# ardunio-physics-board-v2.net
KiCad netlist of a schematic drawn in EAGLE
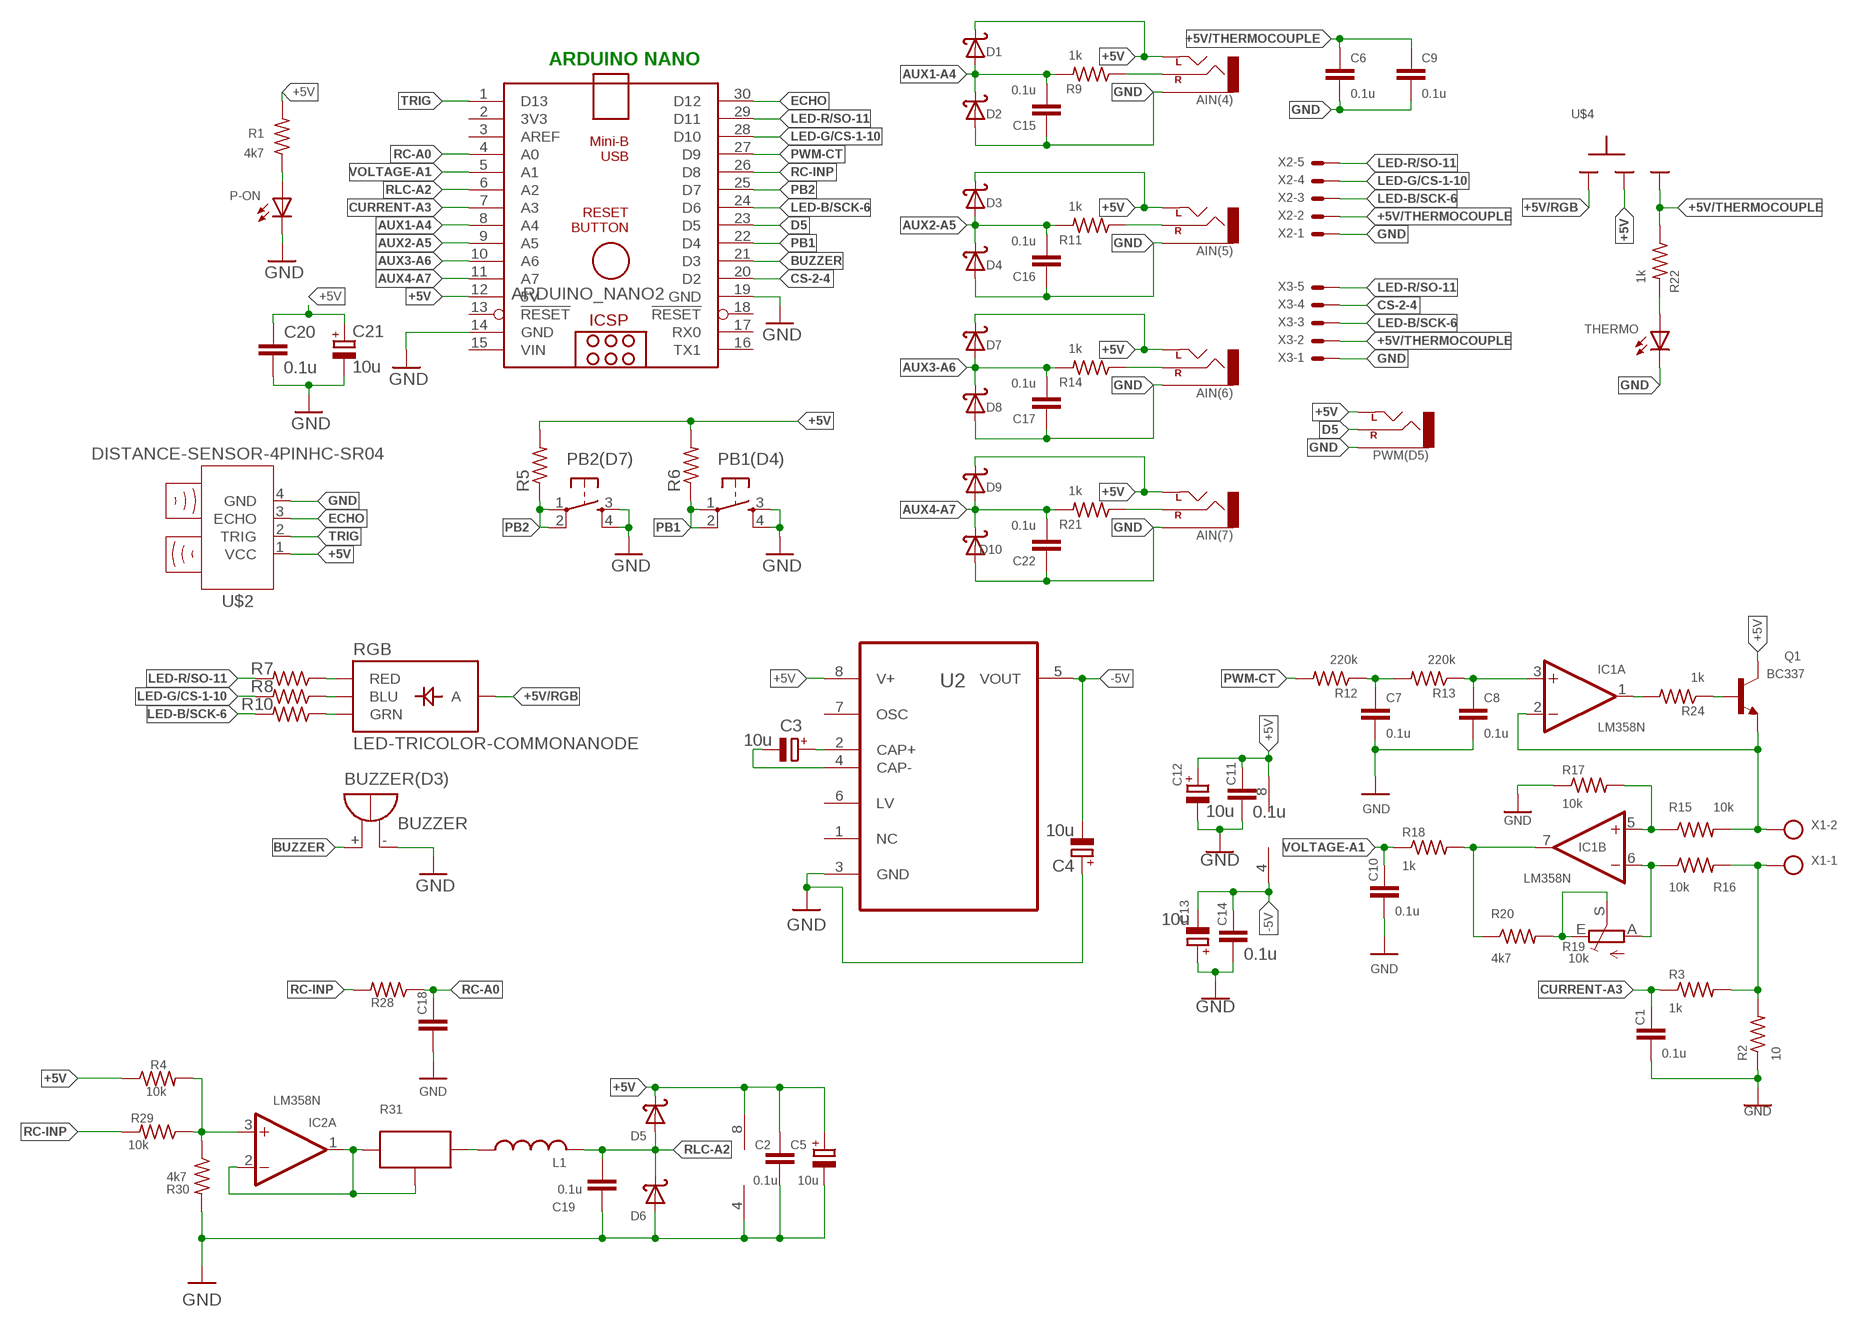
[diagram p0: schematic, sheet 1]

(export (version "E")
  (design (tool "Eeschema 10.0.6"))
  (components
    (comp (ref "AIN(4)")
      (value "AUX-CONNECTOR_CEDT_JANUARY_2015_V5_AUDIO-JACKPTH")
      (footprint "eagle-import:AUX-CONNECTOR_CEDT_JANUARY_2015_V5_AUDIO-JACK")
      (libsource (lib "eagle-import") (part "AUX-CONNECTOR_CEDT_JANUARY_2015_V5_AUDIO-JACKPTH"))
    )
    (comp (ref "AIN(5)")
      (value "AUX-CONNECTOR_CEDT_JANUARY_2015_V5_AUDIO-JACKPTH")
      (footprint "eagle-import:AUX-CONNECTOR_CEDT_JANUARY_2015_V5_AUDIO-JACK")
      (libsource (lib "eagle-import") (part "AUX-CONNECTOR_CEDT_JANUARY_2015_V5_AUDIO-JACKPTH"))
    )
    (comp (ref "AIN(6)")
      (value "AUX-CONNECTOR_CEDT_JANUARY_2015_V5_AUDIO-JACKPTH")
      (footprint "eagle-import:AUX-CONNECTOR_CEDT_JANUARY_2015_V5_AUDIO-JACK")
      (libsource (lib "eagle-import") (part "AUX-CONNECTOR_CEDT_JANUARY_2015_V5_AUDIO-JACKPTH"))
    )
    (comp (ref "AIN(7)")
      (value "AUX-CONNECTOR_CEDT_JANUARY_2015_V5_AUDIO-JACKPTH")
      (footprint "eagle-import:AUX-CONNECTOR_CEDT_JANUARY_2015_V5_AUDIO-JACK")
      (libsource (lib "eagle-import") (part "AUX-CONNECTOR_CEDT_JANUARY_2015_V5_AUDIO-JACKPTH"))
    )
    (comp (ref "ARDUINO_NANO2")
      (value "ARDUINONANOV30_ARDUINO_NANO")
      (footprint "eagle-import:ARDUINONANOV30_ARDUINO_NANO")
      (libsource (lib "eagle-import") (part "ARDUINONANOV30_ARDUINO_NANO"))
    )
    (comp (ref "BUZZER(D3)")
      (value "BUZZER")
      (footprint "eagle-import:F_TMB")
      (libsource (lib "eagle-import") (part "BUZZER"))
    )
    (comp (ref "C1")
      (value "0.1u")
      (footprint "eagle-import:C025-025X050")
      (libsource (lib "eagle-import") (part "C-EU025-025X050"))
    )
    (comp (ref "C2")
      (value "0.1u")
      (footprint "eagle-import:C025-025X050")
      (libsource (lib "eagle-import") (part "C-EU025-025X050"))
    )
    (comp (ref "C3")
      (value "10u")
      (footprint "eagle-import:TT2D5")
      (libsource (lib "eagle-import") (part "CPOL-EUTT2D5"))
    )
    (comp (ref "C4")
      (value "10u")
      (footprint "eagle-import:TT2D5")
      (libsource (lib "eagle-import") (part "CPOL-EUTT2D5"))
    )
    (comp (ref "C5")
      (value "10u")
      (footprint "eagle-import:TT2D5")
      (libsource (lib "eagle-import") (part "CPOL-EUTT2D5"))
    )
    (comp (ref "C6")
      (value "0.1u")
      (footprint "eagle-import:C025-024X044")
      (libsource (lib "eagle-import") (part "C-EU025-024X044"))
    )
    (comp (ref "C7")
      (value "0.1u")
      (footprint "eagle-import:C025-025X050")
      (libsource (lib "eagle-import") (part "C-EU025-025X050"))
    )
    (comp (ref "C8")
      (value "0.1u")
      (footprint "eagle-import:C025-025X050")
      (libsource (lib "eagle-import") (part "C-EU025-025X050"))
    )
    (comp (ref "C9")
      (value "0.1u")
      (footprint "eagle-import:C025-024X044")
      (libsource (lib "eagle-import") (part "C-EU025-024X044"))
    )
    (comp (ref "C10")
      (value "0.1u")
      (footprint "eagle-import:C025-025X050")
      (libsource (lib "eagle-import") (part "C-EU025-025X050"))
    )
    (comp (ref "C11")
      (value "0.1u")
      (footprint "eagle-import:C025-025X050")
      (libsource (lib "eagle-import") (part "C-EU025-025X050"))
    )
    (comp (ref "C12")
      (value "10u")
      (footprint "eagle-import:TT2D5")
      (libsource (lib "eagle-import") (part "CPOL-EUTT2D5"))
    )
    (comp (ref "C13")
      (value "10u")
      (footprint "eagle-import:TT2D5")
      (libsource (lib "eagle-import") (part "CPOL-EUTT2D5"))
    )
    (comp (ref "C14")
      (value "0.1u")
      (footprint "eagle-import:C025-025X050")
      (libsource (lib "eagle-import") (part "C-EU025-025X050"))
    )
    (comp (ref "C15")
      (value "0.1u")
      (footprint "eagle-import:C025-024X044")
      (libsource (lib "eagle-import") (part "C-EU025-024X044"))
    )
    (comp (ref "C16")
      (value "0.1u")
      (footprint "eagle-import:C025-024X044")
      (libsource (lib "eagle-import") (part "C-EU025-024X044"))
    )
    (comp (ref "C17")
      (value "0.1u")
      (footprint "eagle-import:C025-024X044")
      (libsource (lib "eagle-import") (part "C-EU025-024X044"))
    )
    (comp (ref "C18")
      (value "C-EU025-025X050")
      (footprint "eagle-import:C025-025X050")
      (libsource (lib "eagle-import") (part "C-EU025-025X050"))
    )
    (comp (ref "C19")
      (value "0.1u")
      (footprint "eagle-import:C025-025X050")
      (libsource (lib "eagle-import") (part "C-EU025-025X050"))
    )
    (comp (ref "C20")
      (value "0.1u")
      (footprint "eagle-import:C025-024X044")
      (libsource (lib "eagle-import") (part "C-EU025-024X044"))
    )
    (comp (ref "C21")
      (value "10u")
      (footprint "eagle-import:E2,5-5")
      (libsource (lib "eagle-import") (part "CPOL-EUE2.5-5"))
    )
    (comp (ref "C22")
      (value "0.1u")
      (footprint "eagle-import:C025-024X044")
      (libsource (lib "eagle-import") (part "C-EU025-024X044"))
    )
    (comp (ref "D1")
      (value "1N5819")
      (footprint "eagle-import:DO41-10")
      (libsource (lib "eagle-import") (part "1N5819"))
    )
    (comp (ref "D2")
      (value "1N5819")
      (footprint "eagle-import:DO41-10")
      (libsource (lib "eagle-import") (part "1N5819"))
    )
    (comp (ref "D3")
      (value "1N5819")
      (footprint "eagle-import:DO41-10")
      (libsource (lib "eagle-import") (part "1N5819"))
    )
    (comp (ref "D4")
      (value "1N5819")
      (footprint "eagle-import:DO41-10")
      (libsource (lib "eagle-import") (part "1N5819"))
    )
    (comp (ref "D5")
      (value "1N5819")
      (footprint "eagle-import:DO41-10")
      (libsource (lib "eagle-import") (part "1N5819"))
    )
    (comp (ref "D6")
      (value "1N5819")
      (footprint "eagle-import:DO41-10")
      (libsource (lib "eagle-import") (part "1N5819"))
    )
    (comp (ref "D7")
      (value "1N5819")
      (footprint "eagle-import:DO41-10")
      (libsource (lib "eagle-import") (part "1N5819"))
    )
    (comp (ref "D8")
      (value "1N5819")
      (footprint "eagle-import:DO41-10")
      (libsource (lib "eagle-import") (part "1N5819"))
    )
    (comp (ref "D9")
      (value "1N5819")
      (footprint "eagle-import:DO41-10")
      (libsource (lib "eagle-import") (part "1N5819"))
    )
    (comp (ref "D10")
      (value "1N5819")
      (footprint "eagle-import:DO41-10")
      (libsource (lib "eagle-import") (part "1N5819"))
    )
    (comp (ref "IC1")
      (value "LM358N")
      (footprint "eagle-import:DIL08")
      (libsource (lib "eagle-import") (part "LM358N"))
    )
    (comp (ref "IC2")
      (value "LM358N")
      (footprint "eagle-import:DIL08")
      (libsource (lib "eagle-import") (part "LM358N"))
    )
    (comp (ref "L1")
      (value "L-US6000-XXX-RC")
      (footprint "eagle-import:6000-XXXX-RC")
      (libsource (lib "eagle-import") (part "L-US6000-XXX-RC"))
    )
    (comp (ref "P-ON")
      (value "LED3MM")
      (footprint "eagle-import:LED3MM")
      (libsource (lib "eagle-import") (part "LED3MM"))
    )
    (comp (ref "PB1(D4)")
      (value "OMRON_SWITCH_40-XX")
      (footprint "eagle-import:B3F-40XX")
      (libsource (lib "eagle-import") (part "OMRON_SWITCH_40-XX"))
    )
    (comp (ref "PB2(D7)")
      (value "OMRON_SWITCH_40-XX")
      (footprint "eagle-import:B3F-40XX")
      (libsource (lib "eagle-import") (part "OMRON_SWITCH_40-XX"))
    )
    (comp (ref "PWM(D5)")
      (value "AUX-CONNECTOR_CEDT_JANUARY_2015_V5_AUDIO-JACKPTH")
      (footprint "eagle-import:AUX-CONNECTOR_CEDT_JANUARY_2015_V5_AUDIO-JACK")
      (libsource (lib "eagle-import") (part "AUX-CONNECTOR_CEDT_JANUARY_2015_V5_AUDIO-JACKPTH"))
    )
    (comp (ref "Q1")
      (value "BC337")
      (footprint "eagle-import:TO92")
      (libsource (lib "eagle-import") (part "BC337"))
    )
    (comp (ref "R1")
      (value "4k7")
      (footprint "eagle-import:0204_7")
      (libsource (lib "eagle-import") (part "R-US_0204/7"))
    )
    (comp (ref "R2")
      (value "10")
      (footprint "eagle-import:0207_10")
      (libsource (lib "eagle-import") (part "RESISTOR0207/10"))
    )
    (comp (ref "R3")
      (value "1k")
      (footprint "eagle-import:0204_7")
      (libsource (lib "eagle-import") (part "R-US_0204/7"))
    )
    (comp (ref "R4")
      (value "10k")
      (footprint "eagle-import:0207_10")
      (libsource (lib "eagle-import") (part "R-US_0207/10"))
    )
    (comp (ref "R5")
      (value "R-US_0204/7")
      (footprint "eagle-import:0204_7")
      (libsource (lib "eagle-import") (part "R-US_0204/7"))
    )
    (comp (ref "R6")
      (value "R-US_0204/7")
      (footprint "eagle-import:0204_7")
      (libsource (lib "eagle-import") (part "R-US_0204/7"))
    )
    (comp (ref "R7")
      (value "R-US_0207/10")
      (footprint "eagle-import:0207_10")
      (libsource (lib "eagle-import") (part "R-US_0207/10"))
    )
    (comp (ref "R8")
      (value "R-US_0207/10")
      (footprint "eagle-import:0207_10")
      (libsource (lib "eagle-import") (part "R-US_0207/10"))
    )
    (comp (ref "R9")
      (value "1k")
      (footprint "eagle-import:0204_7")
      (libsource (lib "eagle-import") (part "R-US_0204/7"))
    )
    (comp (ref "R10")
      (value "R-US_0207/10")
      (footprint "eagle-import:0207_10")
      (libsource (lib "eagle-import") (part "R-US_0207/10"))
    )
    (comp (ref "R11")
      (value "1k")
      (footprint "eagle-import:0204_7")
      (libsource (lib "eagle-import") (part "R-US_0204/7"))
    )
    (comp (ref "R12")
      (value "220k")
      (footprint "eagle-import:0207_10")
      (libsource (lib "eagle-import") (part "R-US_0207/10"))
    )
    (comp (ref "R13")
      (value "220k")
      (footprint "eagle-import:0204_7")
      (libsource (lib "eagle-import") (part "R-US_0204/7"))
    )
    (comp (ref "R14")
      (value "1k")
      (footprint "eagle-import:0204_7")
      (libsource (lib "eagle-import") (part "R-US_0204/7"))
    )
    (comp (ref "R15")
      (value "10k")
      (footprint "eagle-import:0204_7")
      (libsource (lib "eagle-import") (part "R-US_0204/7"))
    )
    (comp (ref "R16")
      (value "10k")
      (footprint "eagle-import:0204_7")
      (libsource (lib "eagle-import") (part "R-US_0204/7"))
    )
    (comp (ref "R17")
      (value "10k")
      (footprint "eagle-import:0204_7")
      (libsource (lib "eagle-import") (part "R-US_0204/7"))
    )
    (comp (ref "R18")
      (value "1k")
      (footprint "eagle-import:0204_7")
      (libsource (lib "eagle-import") (part "R-US_0204/7"))
    )
    (comp (ref "R19")
      (value "10k")
      (footprint "eagle-import:RJ9W")
      (libsource (lib "eagle-import") (part "TRIM_EU-RJ9W"))
    )
    (comp (ref "R20")
      (value "4k7")
      (footprint "eagle-import:0204_7")
      (libsource (lib "eagle-import") (part "R-US_0204/7"))
    )
    (comp (ref "R21")
      (value "1k")
      (footprint "eagle-import:0204_7")
      (libsource (lib "eagle-import") (part "R-US_0204/7"))
    )
    (comp (ref "R22")
      (value "1k")
      (footprint "eagle-import:0204_7")
      (libsource (lib "eagle-import") (part "R-US_0204/7"))
    )
    (comp (ref "R24")
      (value "1k")
      (footprint "eagle-import:0204_7")
      (libsource (lib "eagle-import") (part "R-US_0204/7"))
    )
    (comp (ref "R28")
      (value "R-US_0207/10")
      (footprint "eagle-import:0207_10")
      (libsource (lib "eagle-import") (part "R-US_0207/10"))
    )
    (comp (ref "R29")
      (value "10k")
      (footprint "eagle-import:0204_7")
      (libsource (lib "eagle-import") (part "R-US_0204/7"))
    )
    (comp (ref "R30")
      (value "4k7")
      (footprint "eagle-import:0207_10")
      (libsource (lib "eagle-import") (part "R-US_0207/10"))
    )
    (comp (ref "R31")
      (value "POTNORMAL")
      (footprint "eagle-import:RJ9W")
      (libsource (lib "eagle-import") (part "POTNORMAL"))
    )
    (comp (ref "RGB")
      (value "LED-TRICOLOR-COMMONANODE")
      (footprint "eagle-import:LED-TRICOLOR-THROUGHHOLE")
      (libsource (lib "eagle-import") (part "LED-TRICOLOR-COMMONANODE"))
    )
    (comp (ref "THERMO")
      (value "LED3MM")
      (footprint "eagle-import:LED3MM")
      (libsource (lib "eagle-import") (part "LED3MM"))
    )
    (comp (ref "U$2")
      (value "DISTANCE-SENSOR-4PINHC-SR04")
      (footprint "eagle-import:HC-SR04")
      (libsource (lib "eagle-import") (part "DISTANCE-SENSOR-4PINHC-SR04"))
    )
    (comp (ref "U$4")
      (value "SLIDESWITCH-BIG")
      (footprint "eagle-import:BIGSWITCH")
      (libsource (lib "eagle-import") (part "SLIDESWITCH-BIG"))
    )
    (comp (ref "U2")
      (value "ICL7660CPAZ_ICL7660CPAZ")
      (footprint "eagle-import:ICL7660CPAZ_DIP254P762X533-8")
      (fields (field (name "MF") "Renesas Electronics") (field (name "MP") "ICL7660CPAZ"))
      (libsource (lib "eagle-import") (part "ICL7660CPAZ_ICL7660CPAZ"))
    )
    (comp (ref "X1")
      (value "AK500/2-H")
      (footprint "eagle-import:AK500_2-H")
      (libsource (lib "eagle-import") (part "AK500/2-H"))
    )
    (comp (ref "X2")
      (value "JST-XH-05-PIN-LONG-PAD")
      (footprint "eagle-import:JST-XH-05-PACKAGE-LONG-PAD")
      (libsource (lib "eagle-import") (part "JST-XH-05-PIN-LONG-PAD"))
    )
    (comp (ref "X3")
      (value "JST-XH-05-PIN-LONG-PAD")
      (footprint "eagle-import:JST-XH-05-PACKAGE-LONG-PAD")
      (libsource (lib "eagle-import") (part "JST-XH-05-PIN-LONG-PAD"))
    )
  )
  (nets
    (net (code "1") (name "+5V") (class "Default")
      (node (ref "AIN(4)") (pin "TIP") (pinfunction "LEFT_TIP") (pintype "bidirectional"))
      (node (ref "AIN(5)") (pin "TIP") (pinfunction "LEFT_TIP") (pintype "bidirectional"))
      (node (ref "AIN(6)") (pin "TIP") (pinfunction "LEFT_TIP") (pintype "bidirectional"))
      (node (ref "AIN(7)") (pin "TIP") (pinfunction "LEFT_TIP") (pintype "bidirectional"))
      (node (ref "ARDUINO_NANO2") (pin "12") (pinfunction "5V_12") (pintype "power_in"))
      (node (ref "C11") (pin "1") (pinfunction "1_1") (pintype "passive"))
      (node (ref "C12") (pin "+") (pinfunction "+_+") (pintype "passive"))
      (node (ref "C2") (pin "1") (pinfunction "1_1") (pintype "passive"))
      (node (ref "C20") (pin "1") (pinfunction "1_1") (pintype "passive"))
      (node (ref "C21") (pin "+") (pinfunction "+_+") (pintype "passive"))
      (node (ref "C5") (pin "+") (pinfunction "+_+") (pintype "passive"))
      (node (ref "D1") (pin "C") (pinfunction "C_C") (pintype "passive"))
      (node (ref "D3") (pin "C") (pinfunction "C_C") (pintype "passive"))
      (node (ref "D5") (pin "C") (pinfunction "C_C") (pintype "passive"))
      (node (ref "D7") (pin "C") (pinfunction "C_C") (pintype "passive"))
      (node (ref "D9") (pin "C") (pinfunction "C_C") (pintype "passive"))
      (node (ref "IC1") (pin "8") (pinfunction "V+_8") (pintype "power_in"))
      (node (ref "IC2") (pin "8") (pinfunction "V+_8") (pintype "power_in"))
      (node (ref "PWM(D5)") (pin "TIP") (pinfunction "LEFT_TIP") (pintype "bidirectional"))
      (node (ref "Q1") (pin "3") (pinfunction "C_3") (pintype "passive"))
      (node (ref "R1") (pin "2") (pinfunction "2_2") (pintype "passive"))
      (node (ref "R4") (pin "1") (pinfunction "1_1") (pintype "passive"))
      (node (ref "R5") (pin "2") (pinfunction "2_2") (pintype "passive"))
      (node (ref "R6") (pin "2") (pinfunction "2_2") (pintype "passive"))
      (node (ref "U$2") (pin "1") (pinfunction "VCC_1") (pintype "bidirectional"))
      (node (ref "U$4") (pin "2") (pinfunction "2_2") (pintype "bidirectional"))
      (node (ref "U2") (pin "8") (pinfunction "V+_8") (pintype "power_in"))
    )
    (net (code "2") (name "+5V{slash}RGB") (class "Default")
      (node (ref "RGB") (pin "ANODE") (pinfunction "A_ANODE") (pintype "bidirectional"))
      (node (ref "U$4") (pin "1") (pinfunction "1_1") (pintype "bidirectional"))
    )
    (net (code "3") (name "+5V{slash}THERMOCOUPLE") (class "Default")
      (node (ref "C6") (pin "1") (pinfunction "1_1") (pintype "passive"))
      (node (ref "C9") (pin "1") (pinfunction "1_1") (pintype "passive"))
      (node (ref "R22") (pin "1") (pinfunction "1_1") (pintype "passive"))
      (node (ref "U$4") (pin "3") (pinfunction "3_3") (pintype "bidirectional"))
      (node (ref "X2") (pin "2") (pinfunction "S_2") (pintype "passive"))
      (node (ref "X3") (pin "2") (pinfunction "S_2") (pintype "passive"))
    )
    (net (code "4") (name "-5V") (class "Default")
      (node (ref "C13") (pin "-") (pinfunction "-_-") (pintype "passive"))
      (node (ref "C14") (pin "1") (pinfunction "1_1") (pintype "passive"))
      (node (ref "C4") (pin "-") (pinfunction "-_-") (pintype "passive"))
      (node (ref "IC1") (pin "4") (pinfunction "V-_4") (pintype "power_in"))
      (node (ref "U2") (pin "5") (pinfunction "VOUT_5") (pintype "output"))
    )
    (net (code "5") (name "/VIN") (class "Default")
      (node (ref "ARDUINO_NANO2") (pin "15") (pinfunction "VIN_15") (pintype "power_in"))
    )
    (net (code "6") (name "AUX1-A4") (class "Default")
      (node (ref "ARDUINO_NANO2") (pin "8") (pinfunction "A4_8") (pintype "bidirectional"))
      (node (ref "C15") (pin "2") (pinfunction "2_2") (pintype "passive"))
      (node (ref "D1") (pin "A") (pinfunction "A_A") (pintype "passive"))
      (node (ref "D2") (pin "C") (pinfunction "C_C") (pintype "passive"))
      (node (ref "R9") (pin "2") (pinfunction "2_2") (pintype "passive"))
    )
    (net (code "7") (name "AUX2-A5") (class "Default")
      (node (ref "ARDUINO_NANO2") (pin "9") (pinfunction "A5_9") (pintype "bidirectional"))
      (node (ref "C16") (pin "2") (pinfunction "2_2") (pintype "passive"))
      (node (ref "D3") (pin "A") (pinfunction "A_A") (pintype "passive"))
      (node (ref "D4") (pin "C") (pinfunction "C_C") (pintype "passive"))
      (node (ref "R11") (pin "2") (pinfunction "2_2") (pintype "passive"))
    )
    (net (code "8") (name "AUX3-A6") (class "Default")
      (node (ref "ARDUINO_NANO2") (pin "10") (pinfunction "A6_10") (pintype "bidirectional"))
      (node (ref "C17") (pin "2") (pinfunction "2_2") (pintype "passive"))
      (node (ref "D7") (pin "A") (pinfunction "A_A") (pintype "passive"))
      (node (ref "D8") (pin "C") (pinfunction "C_C") (pintype "passive"))
      (node (ref "R14") (pin "2") (pinfunction "2_2") (pintype "passive"))
    )
    (net (code "9") (name "AUX4-A7") (class "Default")
      (node (ref "ARDUINO_NANO2") (pin "11") (pinfunction "A7_11") (pintype "bidirectional"))
      (node (ref "C22") (pin "2") (pinfunction "2_2") (pintype "passive"))
      (node (ref "D10") (pin "C") (pinfunction "C_C") (pintype "passive"))
      (node (ref "D9") (pin "A") (pinfunction "A_A") (pintype "passive"))
      (node (ref "R21") (pin "2") (pinfunction "2_2") (pintype "passive"))
    )
    (net (code "10") (name "BUZZER") (class "Default")
      (node (ref "ARDUINO_NANO2") (pin "21") (pinfunction "D3_21") (pintype "bidirectional"))
      (node (ref "BUZZER(D3)") (pin "+") (pinfunction "+_+") (pintype "passive"))
    )
    (net (code "11") (name "CS-2-4") (class "Default")
      (node (ref "ARDUINO_NANO2") (pin "20") (pinfunction "D2_20") (pintype "bidirectional"))
      (node (ref "X3") (pin "4") (pinfunction "S_4") (pintype "passive"))
    )
    (net (code "12") (name "CURRENT-A3") (class "Default")
      (node (ref "ARDUINO_NANO2") (pin "7") (pinfunction "A3_7") (pintype "bidirectional"))
      (node (ref "C1") (pin "1") (pinfunction "1_1") (pintype "passive"))
      (node (ref "R3") (pin "1") (pinfunction "1_1") (pintype "passive"))
    )
    (net (code "13") (name "D5") (class "Default")
      (node (ref "ARDUINO_NANO2") (pin "23") (pinfunction "D5_23") (pintype "bidirectional"))
      (node (ref "PWM(D5)") (pin "RING") (pinfunction "RIGHT_RING") (pintype "bidirectional"))
    )
    (net (code "14") (name "ECHO") (class "Default")
      (node (ref "ARDUINO_NANO2") (pin "30") (pinfunction "D12_30") (pintype "bidirectional"))
      (node (ref "U$2") (pin "3") (pinfunction "ECHO_3") (pintype "bidirectional"))
    )
    (net (code "15") (name "GND") (class "Default")
      (node (ref "AIN(4)") (pin "SLEEVE") (pinfunction "SLEEVE_SLEEVE") (pintype "bidirectional"))
      (node (ref "AIN(5)") (pin "SLEEVE") (pinfunction "SLEEVE_SLEEVE") (pintype "bidirectional"))
      (node (ref "AIN(6)") (pin "SLEEVE") (pinfunction "SLEEVE_SLEEVE") (pintype "bidirectional"))
      (node (ref "AIN(7)") (pin "SLEEVE") (pinfunction "SLEEVE_SLEEVE") (pintype "bidirectional"))
      (node (ref "ARDUINO_NANO2") (pin "14") (pinfunction "GND_14") (pintype "power_in"))
      (node (ref "ARDUINO_NANO2") (pin "19") (pinfunction "GND_19") (pintype "power_in"))
      (node (ref "BUZZER(D3)") (pin "-") (pinfunction "-_-") (pintype "passive"))
      (node (ref "C1") (pin "2") (pinfunction "2_2") (pintype "passive"))
      (node (ref "C10") (pin "2") (pinfunction "2_2") (pintype "passive"))
      (node (ref "C11") (pin "2") (pinfunction "2_2") (pintype "passive"))
      (node (ref "C12") (pin "-") (pinfunction "-_-") (pintype "passive"))
      (node (ref "C13") (pin "+") (pinfunction "+_+") (pintype "passive"))
      (node (ref "C14") (pin "2") (pinfunction "2_2") (pintype "passive"))
      (node (ref "C15") (pin "1") (pinfunction "1_1") (pintype "passive"))
      (node (ref "C16") (pin "1") (pinfunction "1_1") (pintype "passive"))
      (node (ref "C17") (pin "1") (pinfunction "1_1") (pintype "passive"))
      (node (ref "C18") (pin "2") (pinfunction "2_2") (pintype "passive"))
      (node (ref "C19") (pin "2") (pinfunction "2_2") (pintype "passive"))
      (node (ref "C2") (pin "2") (pinfunction "2_2") (pintype "passive"))
      (node (ref "C20") (pin "2") (pinfunction "2_2") (pintype "passive"))
      (node (ref "C21") (pin "-") (pinfunction "-_-") (pintype "passive"))
      (node (ref "C22") (pin "1") (pinfunction "1_1") (pintype "passive"))
      (node (ref "C4") (pin "+") (pinfunction "+_+") (pintype "passive"))
      (node (ref "C5") (pin "-") (pinfunction "-_-") (pintype "passive"))
      (node (ref "C6") (pin "2") (pinfunction "2_2") (pintype "passive"))
      (node (ref "C7") (pin "2") (pinfunction "2_2") (pintype "passive"))
      (node (ref "C8") (pin "2") (pinfunction "2_2") (pintype "passive"))
      (node (ref "C9") (pin "2") (pinfunction "2_2") (pintype "passive"))
      (node (ref "D10") (pin "A") (pinfunction "A_A") (pintype "passive"))
      (node (ref "D2") (pin "A") (pinfunction "A_A") (pintype "passive"))
      (node (ref "D4") (pin "A") (pinfunction "A_A") (pintype "passive"))
      (node (ref "D6") (pin "A") (pinfunction "A_A") (pintype "passive"))
      (node (ref "D8") (pin "A") (pinfunction "A_A") (pintype "passive"))
      (node (ref "IC2") (pin "4") (pinfunction "V-_4") (pintype "power_in"))
      (node (ref "P-ON") (pin "K") (pinfunction "C_K") (pintype "passive"))
      (node (ref "PB1(D4)") (pin "3") (pinfunction "S_3") (pintype "passive"))
      (node (ref "PB1(D4)") (pin "4") (pinfunction "S1_4") (pintype "passive"))
      (node (ref "PB2(D7)") (pin "3") (pinfunction "S_3") (pintype "passive"))
      (node (ref "PB2(D7)") (pin "4") (pinfunction "S1_4") (pintype "passive"))
      (node (ref "PWM(D5)") (pin "SLEEVE") (pinfunction "SLEEVE_SLEEVE") (pintype "bidirectional"))
      (node (ref "R17") (pin "1") (pinfunction "1_1") (pintype "passive"))
      (node (ref "R2") (pin "1") (pinfunction "1_1") (pintype "passive"))
      (node (ref "R30") (pin "2") (pinfunction "2_2") (pintype "passive"))
      (node (ref "THERMO") (pin "K") (pinfunction "C_K") (pintype "passive"))
      (node (ref "U$2") (pin "4") (pinfunction "GND_4") (pintype "bidirectional"))
      (node (ref "U2") (pin "3") (pinfunction "GND_3") (pintype "passive"))
      (node (ref "X2") (pin "1") (pinfunction "S_1") (pintype "passive"))
      (node (ref "X3") (pin "1") (pinfunction "S_1") (pintype "passive"))
    )
    (net (code "16") (name "LED-B{slash}SCK-6") (class "Default")
      (node (ref "ARDUINO_NANO2") (pin "24") (pinfunction "D6_24") (pintype "bidirectional"))
      (node (ref "R10") (pin "2") (pinfunction "2_2") (pintype "passive"))
      (node (ref "X2") (pin "3") (pinfunction "S_3") (pintype "passive"))
      (node (ref "X3") (pin "3") (pinfunction "S_3") (pintype "passive"))
    )
    (net (code "17") (name "LED-G{slash}CS-1-10") (class "Default")
      (node (ref "ARDUINO_NANO2") (pin "28") (pinfunction "D10_28") (pintype "bidirectional"))
      (node (ref "R8") (pin "2") (pinfunction "2_2") (pintype "passive"))
      (node (ref "X2") (pin "4") (pinfunction "S_4") (pintype "passive"))
    )
    (net (code "18") (name "LED-R{slash}SO-11") (class "Default")
      (node (ref "ARDUINO_NANO2") (pin "29") (pinfunction "D11_29") (pintype "bidirectional"))
      (node (ref "R7") (pin "2") (pinfunction "2_2") (pintype "passive"))
      (node (ref "X2") (pin "5") (pinfunction "S_5") (pintype "passive"))
      (node (ref "X3") (pin "5") (pinfunction "S_5") (pintype "passive"))
    )
    (net (code "19") (name "Net-(AIN(4)-RIGHT)") (class "Default")
      (node (ref "AIN(4)") (pin "RING") (pinfunction "RIGHT_RING") (pintype "bidirectional"))
      (node (ref "R9") (pin "1") (pinfunction "1_1") (pintype "passive"))
    )
    (net (code "20") (name "Net-(AIN(5)-RIGHT)") (class "Default")
      (node (ref "AIN(5)") (pin "RING") (pinfunction "RIGHT_RING") (pintype "bidirectional"))
      (node (ref "R11") (pin "1") (pinfunction "1_1") (pintype "passive"))
    )
    (net (code "21") (name "Net-(AIN(6)-RIGHT)") (class "Default")
      (node (ref "AIN(6)") (pin "RING") (pinfunction "RIGHT_RING") (pintype "bidirectional"))
      (node (ref "R14") (pin "1") (pinfunction "1_1") (pintype "passive"))
    )
    (net (code "22") (name "Net-(AIN(7)-RIGHT)") (class "Default")
      (node (ref "AIN(7)") (pin "RING") (pinfunction "RIGHT_RING") (pintype "bidirectional"))
      (node (ref "R21") (pin "1") (pinfunction "1_1") (pintype "passive"))
    )
    (net (code "23") (name "Net-(C7-Pad1)") (class "Default")
      (node (ref "C7") (pin "1") (pinfunction "1_1") (pintype "passive"))
      (node (ref "R12") (pin "1") (pinfunction "1_1") (pintype "passive"))
      (node (ref "R13") (pin "2") (pinfunction "2_2") (pintype "passive"))
    )
    (net (code "24") (name "Net-(IC1A-+IN)") (class "Default")
      (node (ref "C8") (pin "1") (pinfunction "1_1") (pintype "passive"))
      (node (ref "IC1") (pin "3") (pinfunction "+IN_3") (pintype "input"))
      (node (ref "R13") (pin "1") (pinfunction "1_1") (pintype "passive"))
    )
    (net (code "25") (name "Net-(IC1A--IN)") (class "Default")
      (node (ref "IC1") (pin "2") (pinfunction "-IN_2") (pintype "input"))
      (node (ref "Q1") (pin "1") (pinfunction "E_1") (pintype "passive"))
      (node (ref "R15") (pin "2") (pinfunction "2_2") (pintype "passive"))
      (node (ref "X1") (pin "2") (pinfunction "KL_2") (pintype "passive"))
    )
    (net (code "26") (name "Net-(IC1A-OUT)") (class "Default")
      (node (ref "IC1") (pin "1") (pinfunction "OUT_1") (pintype "output"))
      (node (ref "R24") (pin "2") (pinfunction "2_2") (pintype "passive"))
    )
    (net (code "27") (name "Net-(IC1B-+IN)") (class "Default")
      (node (ref "IC1") (pin "5") (pinfunction "+IN_5") (pintype "input"))
      (node (ref "R15") (pin "1") (pinfunction "1_1") (pintype "passive"))
      (node (ref "R17") (pin "2") (pinfunction "2_2") (pintype "passive"))
    )
    (net (code "28") (name "Net-(IC1B--IN)") (class "Default")
      (node (ref "IC1") (pin "6") (pinfunction "-IN_6") (pintype "input"))
      (node (ref "R16") (pin "1") (pinfunction "1_1") (pintype "passive"))
      (node (ref "R19") (pin "A") (pinfunction "A_A") (pintype "passive"))
    )
    (net (code "29") (name "Net-(IC1B-OUT)") (class "Default")
      (node (ref "IC1") (pin "7") (pinfunction "OUT_7") (pintype "output"))
      (node (ref "R18") (pin "2") (pinfunction "2_2") (pintype "passive"))
      (node (ref "R20") (pin "1") (pinfunction "1_1") (pintype "passive"))
    )
    (net (code "30") (name "Net-(IC2A-+IN)") (class "Default")
      (node (ref "IC2") (pin "3") (pinfunction "+IN_3") (pintype "input"))
      (node (ref "R29") (pin "1") (pinfunction "1_1") (pintype "passive"))
      (node (ref "R30") (pin "1") (pinfunction "1_1") (pintype "passive"))
      (node (ref "R4") (pin "2") (pinfunction "2_2") (pintype "passive"))
    )
    (net (code "31") (name "Net-(IC2A--IN)") (class "Default")
      (node (ref "IC2") (pin "1") (pinfunction "OUT_1") (pintype "output"))
      (node (ref "IC2") (pin "2") (pinfunction "-IN_2") (pintype "input"))
      (node (ref "R31") (pin "E") (pinfunction "E_E") (pintype "passive"))
      (node (ref "R31") (pin "S") (pinfunction "S_S") (pintype "passive"))
    )
    (net (code "32") (name "Net-(L1-Pad1)") (class "Default")
      (node (ref "L1") (pin "1") (pinfunction "1_1") (pintype "passive"))
      (node (ref "R31") (pin "A") (pinfunction "A_A") (pintype "passive"))
    )
    (net (code "33") (name "Net-(P-ON-PadA)") (class "Default")
      (node (ref "P-ON") (pin "A") (pinfunction "A_A") (pintype "passive"))
      (node (ref "R1") (pin "1") (pinfunction "1_1") (pintype "passive"))
    )
    (net (code "34") (name "Net-(Q1-B)") (class "Default")
      (node (ref "Q1") (pin "2") (pinfunction "B_2") (pintype "passive"))
      (node (ref "R24") (pin "1") (pinfunction "1_1") (pintype "passive"))
    )
    (net (code "35") (name "Net-(R7-Pad1)") (class "Default")
      (node (ref "R7") (pin "1") (pinfunction "1_1") (pintype "passive"))
      (node (ref "RGB") (pin "RED") (pinfunction "RED_RED") (pintype "bidirectional"))
    )
    (net (code "36") (name "Net-(R8-Pad1)") (class "Default")
      (node (ref "R8") (pin "1") (pinfunction "1_1") (pintype "passive"))
      (node (ref "RGB") (pin "BLU") (pinfunction "BLU_BLU") (pintype "bidirectional"))
    )
    (net (code "37") (name "Net-(R10-Pad1)") (class "Default")
      (node (ref "R10") (pin "1") (pinfunction "1_1") (pintype "passive"))
      (node (ref "RGB") (pin "GRN") (pinfunction "GRN_GRN") (pintype "bidirectional"))
    )
    (net (code "38") (name "Net-(R19-PadE)") (class "Default")
      (node (ref "R19") (pin "E") (pinfunction "E_E") (pintype "passive"))
      (node (ref "R19") (pin "S") (pinfunction "S_S") (pintype "passive"))
      (node (ref "R20") (pin "2") (pinfunction "2_2") (pintype "passive"))
    )
    (net (code "39") (name "Net-(R22-Pad2)") (class "Default")
      (node (ref "R22") (pin "2") (pinfunction "2_2") (pintype "passive"))
      (node (ref "THERMO") (pin "A") (pinfunction "A_A") (pintype "passive"))
    )
    (net (code "40") (name "Net-(U2-CAP+)") (class "Default")
      (node (ref "C3") (pin "+") (pinfunction "+_+") (pintype "passive"))
      (node (ref "U2") (pin "2") (pinfunction "CAP+_2") (pintype "input"))
    )
    (net (code "41") (name "Net-(U2-CAP-)") (class "Default")
      (node (ref "C3") (pin "-") (pinfunction "-_-") (pintype "passive"))
      (node (ref "U2") (pin "4") (pinfunction "CAP-_4") (pintype "input"))
    )
    (net (code "42") (name "Net-(X1A-KL)") (class "Default")
      (node (ref "R16") (pin "2") (pinfunction "2_2") (pintype "passive"))
      (node (ref "R2") (pin "2") (pinfunction "2_2") (pintype "passive"))
      (node (ref "R3") (pin "2") (pinfunction "2_2") (pintype "passive"))
      (node (ref "X1") (pin "1") (pinfunction "KL_1") (pintype "passive"))
    )
    (net (code "43") (name "PB1") (class "Default")
      (node (ref "ARDUINO_NANO2") (pin "22") (pinfunction "D4_22") (pintype "bidirectional"))
      (node (ref "PB1(D4)") (pin "1") (pinfunction "P_1") (pintype "passive"))
      (node (ref "PB1(D4)") (pin "2") (pinfunction "P1_2") (pintype "passive"))
      (node (ref "R6") (pin "1") (pinfunction "1_1") (pintype "passive"))
    )
    (net (code "44") (name "PB2") (class "Default")
      (node (ref "ARDUINO_NANO2") (pin "25") (pinfunction "D7_25") (pintype "bidirectional"))
      (node (ref "PB2(D7)") (pin "1") (pinfunction "P_1") (pintype "passive"))
      (node (ref "PB2(D7)") (pin "2") (pinfunction "P1_2") (pintype "passive"))
      (node (ref "R5") (pin "1") (pinfunction "1_1") (pintype "passive"))
    )
    (net (code "45") (name "PWM-CT") (class "Default")
      (node (ref "ARDUINO_NANO2") (pin "27") (pinfunction "D9_27") (pintype "bidirectional"))
      (node (ref "R12") (pin "2") (pinfunction "2_2") (pintype "passive"))
    )
    (net (code "46") (name "RC-A0") (class "Default")
      (node (ref "ARDUINO_NANO2") (pin "4") (pinfunction "A0_4") (pintype "bidirectional"))
      (node (ref "C18") (pin "1") (pinfunction "1_1") (pintype "passive"))
      (node (ref "R28") (pin "1") (pinfunction "1_1") (pintype "passive"))
    )
    (net (code "47") (name "RC-INP") (class "Default")
      (node (ref "ARDUINO_NANO2") (pin "26") (pinfunction "D8_26") (pintype "bidirectional"))
      (node (ref "R28") (pin "2") (pinfunction "2_2") (pintype "passive"))
      (node (ref "R29") (pin "2") (pinfunction "2_2") (pintype "passive"))
    )
    (net (code "48") (name "RLC-A2") (class "Default")
      (node (ref "ARDUINO_NANO2") (pin "6") (pinfunction "A2_6") (pintype "bidirectional"))
      (node (ref "C19") (pin "1") (pinfunction "1_1") (pintype "passive"))
      (node (ref "D5") (pin "A") (pinfunction "A_A") (pintype "passive"))
      (node (ref "D6") (pin "C") (pinfunction "C_C") (pintype "passive"))
      (node (ref "L1") (pin "2") (pinfunction "2_2") (pintype "passive"))
    )
    (net (code "49") (name "TRIG") (class "Default")
      (node (ref "ARDUINO_NANO2") (pin "1") (pinfunction "D13_1") (pintype "bidirectional"))
      (node (ref "U$2") (pin "2") (pinfunction "TRIG_2") (pintype "bidirectional"))
    )
    (net (code "50") (name "VOLTAGE-A1") (class "Default")
      (node (ref "ARDUINO_NANO2") (pin "5") (pinfunction "A1_5") (pintype "bidirectional"))
      (node (ref "C10") (pin "1") (pinfunction "1_1") (pintype "passive"))
      (node (ref "R18") (pin "1") (pinfunction "1_1") (pintype "passive"))
    )
    (net (code "51") (name "unconnected-(ARDUINO_NANO2-3V3-Pad2)") (class "Default")
      (node (ref "ARDUINO_NANO2") (pin "2") (pinfunction "3V3_2") (pintype "output"))
    )
    (net (code "52") (name "unconnected-(ARDUINO_NANO2-AREF-Pad3)") (class "Default")
      (node (ref "ARDUINO_NANO2") (pin "3") (pinfunction "AREF_3") (pintype "input"))
    )
    (net (code "53") (name "unconnected-(ARDUINO_NANO2-RX0-Pad17)") (class "Default")
      (node (ref "ARDUINO_NANO2") (pin "17") (pinfunction "RX0_17") (pintype "bidirectional"))
    )
    (net (code "54") (name "unconnected-(ARDUINO_NANO2-TX1-Pad16)") (class "Default")
      (node (ref "ARDUINO_NANO2") (pin "16") (pinfunction "TX1_16") (pintype "bidirectional"))
    )
    (net (code "55") (name "unconnected-(ARDUINO_NANO2-~{RESET}-Pad13)") (class "Default")
      (node (ref "ARDUINO_NANO2") (pin "13") (pinfunction "~{RESET}_13") (pintype "input"))
    )
    (net (code "56") (name "unconnected-(ARDUINO_NANO2-~{RESET}-Pad18)") (class "Default")
      (node (ref "ARDUINO_NANO2") (pin "18") (pinfunction "~{RESET}_18") (pintype "input"))
    )
    (net (code "57") (name "unconnected-(U2-LV-Pad6)") (class "Default")
      (node (ref "U2") (pin "6") (pinfunction "LV_6") (pintype "passive"))
    )
    (net (code "58") (name "unconnected-(U2-NC-Pad1)") (class "Default")
      (node (ref "U2") (pin "1") (pinfunction "NC_1") (pintype "no_connect"))
    )
    (net (code "59") (name "unconnected-(U2-OSC-Pad7)") (class "Default")
      (node (ref "U2") (pin "7") (pinfunction "OSC_7") (pintype "input"))
    )
  )
)
